# Adafruit_TCA9548A.net
KiCad netlist of a schematic drawn in EAGLE
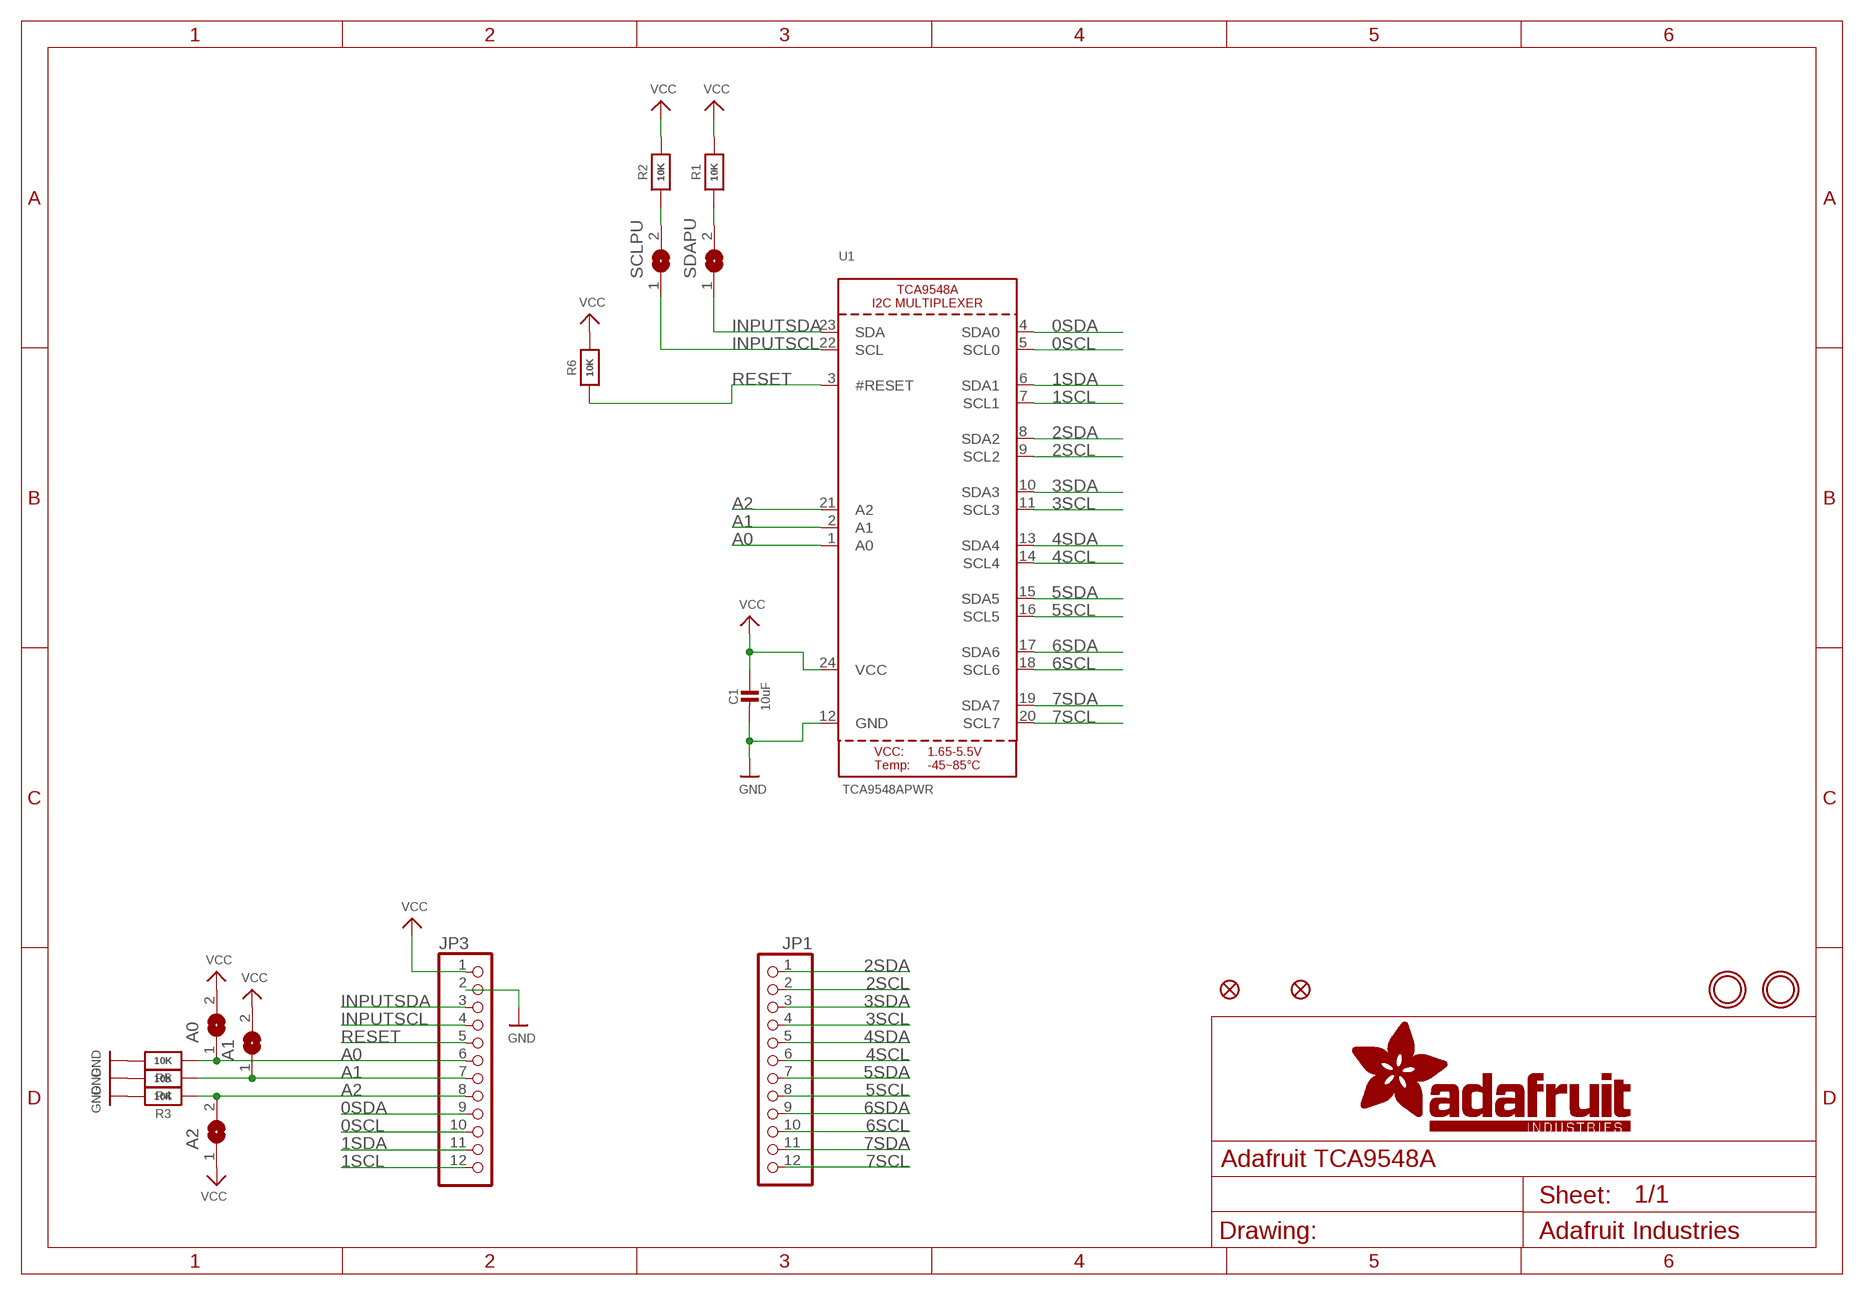
[diagram p0: schematic, sheet 1]

(export (version "E")
  (design (tool "Eeschema 10.0.6"))
  (components
    (comp (ref "A0")
      (value "SOLDERJUMPER")
      (footprint "eagle-import:SOLDERJUMPER_ARROW_NOPASTE")
      (libsource (lib "eagle-import") (part "SOLDERJUMPER"))
    )
    (comp (ref "A1")
      (value "SOLDERJUMPER")
      (footprint "eagle-import:SOLDERJUMPER_ARROW_NOPASTE")
      (libsource (lib "eagle-import") (part "SOLDERJUMPER"))
    )
    (comp (ref "A2")
      (value "SOLDERJUMPER")
      (footprint "eagle-import:SOLDERJUMPER_ARROW_NOPASTE")
      (libsource (lib "eagle-import") (part "SOLDERJUMPER"))
    )
    (comp (ref "C1")
      (value "10uF")
      (footprint "eagle-import:0805-NO")
      (libsource (lib "eagle-import") (part "CAP_CERAMIC0805-NOOUTLINE"))
    )
    (comp (ref "FID1")
      (value "FIDUCIAL\"\"")
      (footprint "eagle-import:FIDUCIAL_1MM")
      (libsource (lib "eagle-import") (part "FIDUCIAL{dblquote}{dblquote}"))
    )
    (comp (ref "FID3")
      (value "FIDUCIAL\"\"")
      (footprint "eagle-import:FIDUCIAL_1MM")
      (libsource (lib "eagle-import") (part "FIDUCIAL{dblquote}{dblquote}"))
    )
    (comp (ref "JP1")
      (value "HEADER-1X12")
      (footprint "eagle-import:1X12_ROUND")
      (libsource (lib "eagle-import") (part "HEADER-1X12"))
    )
    (comp (ref "JP3")
      (value "HEADER-1X12")
      (footprint "eagle-import:1X12_ROUND")
      (libsource (lib "eagle-import") (part "HEADER-1X12"))
    )
    (comp (ref "R1")
      (value "10K")
      (footprint "eagle-import:0805-NO")
      (libsource (lib "eagle-import") (part "RESISTOR0805_NOOUTLINE"))
    )
    (comp (ref "R2")
      (value "10K")
      (footprint "eagle-import:0805-NO")
      (libsource (lib "eagle-import") (part "RESISTOR0805_NOOUTLINE"))
    )
    (comp (ref "R3")
      (value "10K")
      (footprint "eagle-import:0805-NO")
      (libsource (lib "eagle-import") (part "RESISTOR0805_NOOUTLINE"))
    )
    (comp (ref "R4")
      (value "10K")
      (footprint "eagle-import:0805-NO")
      (libsource (lib "eagle-import") (part "RESISTOR0805_NOOUTLINE"))
    )
    (comp (ref "R5")
      (value "10K")
      (footprint "eagle-import:0805-NO")
      (libsource (lib "eagle-import") (part "RESISTOR0805_NOOUTLINE"))
    )
    (comp (ref "R6")
      (value "10K")
      (footprint "eagle-import:_0805MP")
      (libsource (lib "eagle-import") (part "RESISTOR_0805MP"))
    )
    (comp (ref "SCLPU")
      (value "SOLDERJUMPERCLOSED")
      (footprint "eagle-import:SOLDERJUMPER_CLOSEDWIRE")
      (libsource (lib "eagle-import") (part "SOLDERJUMPERCLOSED"))
    )
    (comp (ref "SDAPU")
      (value "SOLDERJUMPERCLOSED")
      (footprint "eagle-import:SOLDERJUMPER_CLOSEDWIRE")
      (libsource (lib "eagle-import") (part "SOLDERJUMPERCLOSED"))
    )
    (comp (ref "U$4")
      (value "MOUNTINGHOLE2.5")
      (footprint "eagle-import:MOUNTINGHOLE_2.5_PLATED")
      (libsource (lib "eagle-import") (part "MOUNTINGHOLE2.5"))
    )
    (comp (ref "U$5")
      (value "MOUNTINGHOLE2.5")
      (footprint "eagle-import:MOUNTINGHOLE_2.5_PLATED")
      (libsource (lib "eagle-import") (part "MOUNTINGHOLE2.5"))
    )
    (comp (ref "U1")
      (value "TCA9548APWR")
      (footprint "eagle-import:TSSOP24")
      (libsource (lib "eagle-import") (part "TCA9548A"))
    )
  )
  (nets
    (net (code "1") (name "/0SCL") (class "Default")
      (node (ref "JP3") (pin "10") (pinfunction "10_10") (pintype "passive"))
      (node (ref "U1") (pin "5") (pinfunction "SCL0_5") (pintype "bidirectional"))
    )
    (net (code "2") (name "/0SDA") (class "Default")
      (node (ref "JP3") (pin "9") (pinfunction "9_9") (pintype "passive"))
      (node (ref "U1") (pin "4") (pinfunction "SDA0_4") (pintype "bidirectional"))
    )
    (net (code "3") (name "/1SCL") (class "Default")
      (node (ref "JP3") (pin "12") (pinfunction "12_12") (pintype "passive"))
      (node (ref "U1") (pin "7") (pinfunction "SCL1_7") (pintype "bidirectional"))
    )
    (net (code "4") (name "/1SDA") (class "Default")
      (node (ref "JP3") (pin "11") (pinfunction "11_11") (pintype "passive"))
      (node (ref "U1") (pin "6") (pinfunction "SDA1_6") (pintype "bidirectional"))
    )
    (net (code "5") (name "/2SCL") (class "Default")
      (node (ref "JP1") (pin "2") (pinfunction "2_2") (pintype "passive"))
      (node (ref "U1") (pin "9") (pinfunction "SCL2_9") (pintype "bidirectional"))
    )
    (net (code "6") (name "/2SDA") (class "Default")
      (node (ref "JP1") (pin "1") (pinfunction "1_1") (pintype "passive"))
      (node (ref "U1") (pin "8") (pinfunction "SDA2_8") (pintype "bidirectional"))
    )
    (net (code "7") (name "/3SCL") (class "Default")
      (node (ref "JP1") (pin "4") (pinfunction "4_4") (pintype "passive"))
      (node (ref "U1") (pin "11") (pinfunction "SCL3_11") (pintype "bidirectional"))
    )
    (net (code "8") (name "/3SDA") (class "Default")
      (node (ref "JP1") (pin "3") (pinfunction "3_3") (pintype "passive"))
      (node (ref "U1") (pin "10") (pinfunction "SDA3_10") (pintype "bidirectional"))
    )
    (net (code "9") (name "/4SCL") (class "Default")
      (node (ref "JP1") (pin "6") (pinfunction "6_6") (pintype "passive"))
      (node (ref "U1") (pin "14") (pinfunction "SCL4_14") (pintype "bidirectional"))
    )
    (net (code "10") (name "/4SDA") (class "Default")
      (node (ref "JP1") (pin "5") (pinfunction "5_5") (pintype "passive"))
      (node (ref "U1") (pin "13") (pinfunction "SDA4_13") (pintype "bidirectional"))
    )
    (net (code "11") (name "/5SCL") (class "Default")
      (node (ref "JP1") (pin "8") (pinfunction "8_8") (pintype "passive"))
      (node (ref "U1") (pin "16") (pinfunction "SCL5_16") (pintype "bidirectional"))
    )
    (net (code "12") (name "/5SDA") (class "Default")
      (node (ref "JP1") (pin "7") (pinfunction "7_7") (pintype "passive"))
      (node (ref "U1") (pin "15") (pinfunction "SDA5_15") (pintype "bidirectional"))
    )
    (net (code "13") (name "/6SCL") (class "Default")
      (node (ref "JP1") (pin "10") (pinfunction "10_10") (pintype "passive"))
      (node (ref "U1") (pin "18") (pinfunction "SCL6_18") (pintype "bidirectional"))
    )
    (net (code "14") (name "/6SDA") (class "Default")
      (node (ref "JP1") (pin "9") (pinfunction "9_9") (pintype "passive"))
      (node (ref "U1") (pin "17") (pinfunction "SDA6_17") (pintype "bidirectional"))
    )
    (net (code "15") (name "/7SCL") (class "Default")
      (node (ref "JP1") (pin "12") (pinfunction "12_12") (pintype "passive"))
      (node (ref "U1") (pin "20") (pinfunction "SCL7_20") (pintype "bidirectional"))
    )
    (net (code "16") (name "/7SDA") (class "Default")
      (node (ref "JP1") (pin "11") (pinfunction "11_11") (pintype "passive"))
      (node (ref "U1") (pin "19") (pinfunction "SDA7_19") (pintype "bidirectional"))
    )
    (net (code "17") (name "/A0") (class "Default")
      (node (ref "A0") (pin "1") (pinfunction "1_1") (pintype "passive"))
      (node (ref "JP3") (pin "6") (pinfunction "6_6") (pintype "passive"))
      (node (ref "R5") (pin "1") (pinfunction "1_1") (pintype "passive"))
      (node (ref "U1") (pin "1") (pinfunction "A0_1") (pintype "bidirectional"))
    )
    (net (code "18") (name "/A1") (class "Default")
      (node (ref "A1") (pin "1") (pinfunction "1_1") (pintype "passive"))
      (node (ref "JP3") (pin "7") (pinfunction "7_7") (pintype "passive"))
      (node (ref "R4") (pin "1") (pinfunction "1_1") (pintype "passive"))
      (node (ref "U1") (pin "2") (pinfunction "A1_2") (pintype "bidirectional"))
    )
    (net (code "19") (name "/A2") (class "Default")
      (node (ref "A2") (pin "2") (pinfunction "2_2") (pintype "passive"))
      (node (ref "JP3") (pin "8") (pinfunction "8_8") (pintype "passive"))
      (node (ref "R3") (pin "1") (pinfunction "1_1") (pintype "passive"))
      (node (ref "U1") (pin "21") (pinfunction "A2_21") (pintype "bidirectional"))
    )
    (net (code "20") (name "/INPUTSCL") (class "Default")
      (node (ref "JP3") (pin "4") (pinfunction "4_4") (pintype "passive"))
      (node (ref "SCLPU") (pin "1") (pinfunction "1_1") (pintype "passive"))
      (node (ref "U1") (pin "22") (pinfunction "SCL_22") (pintype "bidirectional"))
    )
    (net (code "21") (name "/INPUTSDA") (class "Default")
      (node (ref "JP3") (pin "3") (pinfunction "3_3") (pintype "passive"))
      (node (ref "SDAPU") (pin "1") (pinfunction "1_1") (pintype "passive"))
      (node (ref "U1") (pin "23") (pinfunction "SDA_23") (pintype "bidirectional"))
    )
    (net (code "22") (name "/RESET") (class "Default")
      (node (ref "JP3") (pin "5") (pinfunction "5_5") (pintype "passive"))
      (node (ref "R6") (pin "1") (pinfunction "1_1") (pintype "passive"))
      (node (ref "U1") (pin "3") (pinfunction "#RESET_3") (pintype "bidirectional"))
    )
    (net (code "23") (name "GND") (class "Default")
      (node (ref "C1") (pin "2") (pinfunction "2_2") (pintype "passive"))
      (node (ref "JP3") (pin "2") (pinfunction "2_2") (pintype "passive"))
      (node (ref "R3") (pin "2") (pinfunction "2_2") (pintype "passive"))
      (node (ref "R4") (pin "2") (pinfunction "2_2") (pintype "passive"))
      (node (ref "R5") (pin "2") (pinfunction "2_2") (pintype "passive"))
      (node (ref "U1") (pin "12") (pinfunction "GND_12") (pintype "bidirectional"))
    )
    (net (code "24") (name "Net-(R1-Pad1)") (class "Default")
      (node (ref "R1") (pin "1") (pinfunction "1_1") (pintype "passive"))
      (node (ref "SDAPU") (pin "2") (pinfunction "2_2") (pintype "passive"))
    )
    (net (code "25") (name "Net-(R2-Pad1)") (class "Default")
      (node (ref "R2") (pin "1") (pinfunction "1_1") (pintype "passive"))
      (node (ref "SCLPU") (pin "2") (pinfunction "2_2") (pintype "passive"))
    )
    (net (code "26") (name "VCC") (class "Default")
      (node (ref "A0") (pin "2") (pinfunction "2_2") (pintype "passive"))
      (node (ref "A1") (pin "2") (pinfunction "2_2") (pintype "passive"))
      (node (ref "A2") (pin "1") (pinfunction "1_1") (pintype "passive"))
      (node (ref "C1") (pin "1") (pinfunction "1_1") (pintype "passive"))
      (node (ref "JP3") (pin "1") (pinfunction "1_1") (pintype "passive"))
      (node (ref "R1") (pin "2") (pinfunction "2_2") (pintype "passive"))
      (node (ref "R2") (pin "2") (pinfunction "2_2") (pintype "passive"))
      (node (ref "R6") (pin "2") (pinfunction "2_2") (pintype "passive"))
      (node (ref "U1") (pin "24") (pinfunction "VCC_24") (pintype "bidirectional"))
    )
  )
)
